# Ethernet_Phy.net
KiCad netlist of a schematic drawn in Altium Designer
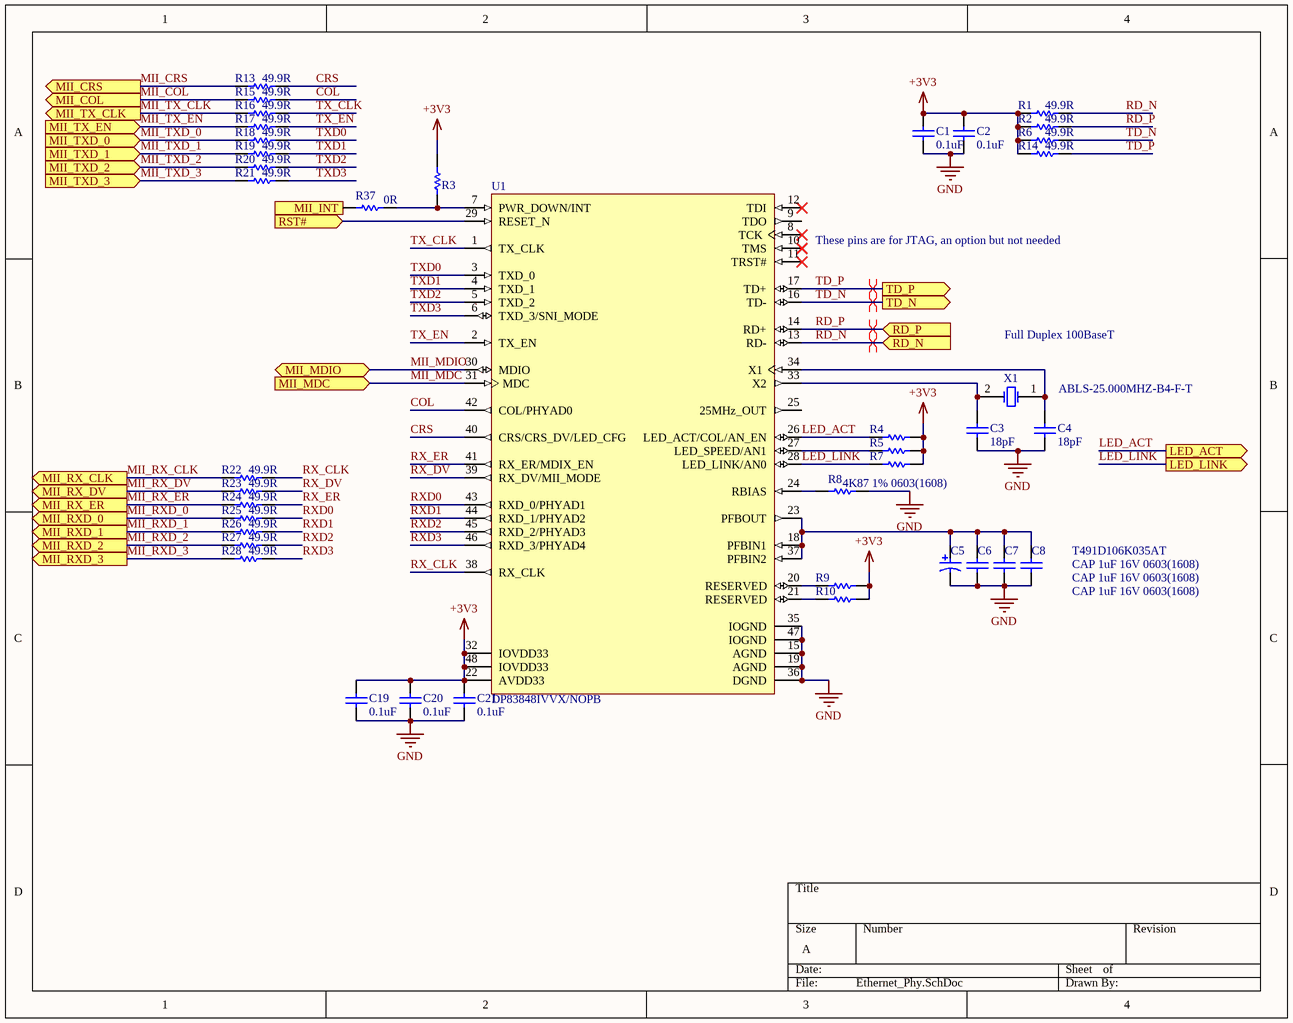
[diagram p0: Ethernet_Phy.SchDoc]

(export (version "E")
  (design (tool "Eeschema 10.0.6"))
  (components
    (comp (ref "C1")
      (value "0.1uF")
      (footprint "CAPC0603(1608)100_L")
      (description "0603 (1608 Metric) Chip Capacitor")
      (libsource (lib "Altium Content Vault") (part "CAP_5"))
    )
    (comp (ref "C2")
      (value "0.1uF")
      (footprint "CAPC0603(1608)100_L")
      (description "0603 (1608 Metric) Chip Capacitor")
      (libsource (lib "Altium Content Vault") (part "CAP_5"))
    )
    (comp (ref "C3")
      (value "18pF")
      (footprint "CAPC0603(1608)100_L")
      (description "0603 (1608 Metric) Chip Capacitor")
      (libsource (lib "Altium Content Vault") (part "CAP_5"))
    )
    (comp (ref "C4")
      (value "18pF")
      (footprint "CAPC0603(1608)100_L")
      (description "0603 (1608 Metric) Chip Capacitor")
      (libsource (lib "Altium Content Vault") (part "CAP_5"))
    )
    (comp (ref "C5")
      (value "T491D106K035AT")
      (footprint "KEMT-T491-D_L")
      (description "Tantalum Capacitor, 10 uF, +/- 10%, 35 V, -55 to 125 degC, 2-Pin SMD, RoHS, Tape and Reel")
      (fields (field (name "MANUFACTURER") "Kemet") (field (name "TOLERANCE") "20%"))
      (libsource (lib "Altium Content Vault") (part "CAP-P-2"))
    )
    (comp (ref "C6")
      (value "CAP 1uF 16V 0603(1608)")
      (footprint "CAPC0603(1608)100_N")
      (description "CAP 1uF 16V ±5% 0603 (1608 Metric) Thickness 1mm SMD")
      (fields (field (name "TOLERANCE") "Â±5%"))
      (libsource (lib "Altium Content Vault") (part "CAP"))
    )
    (comp (ref "C7")
      (value "CAP 1uF 16V 0603(1608)")
      (footprint "CAPC0603(1608)100_N")
      (description "CAP 1uF 16V ±5% 0603 (1608 Metric) Thickness 1mm SMD")
      (fields (field (name "TOLERANCE") "Â±5%"))
      (libsource (lib "Altium Content Vault") (part "CAP"))
    )
    (comp (ref "C8")
      (value "CAP 1uF 16V 0603(1608)")
      (footprint "CAPC0603(1608)100_N")
      (description "CAP 1uF 16V ±5% 0603 (1608 Metric) Thickness 1mm SMD")
      (fields (field (name "TOLERANCE") "Â±5%"))
      (libsource (lib "Altium Content Vault") (part "CAP"))
    )
    (comp (ref "C19")
      (value "0.1uF")
      (footprint "CAPC0603(1608)100_L")
      (description "0603 (1608 Metric) Chip Capacitor")
      (libsource (lib "Altium Content Vault") (part "CAP_5"))
    )
    (comp (ref "C20")
      (value "0.1uF")
      (footprint "CAPC0603(1608)100_L")
      (description "0603 (1608 Metric) Chip Capacitor")
      (libsource (lib "Altium Content Vault") (part "CAP_5"))
    )
    (comp (ref "C21")
      (value "0.1uF")
      (footprint "CAPC0603(1608)100_L")
      (description "0603 (1608 Metric) Chip Capacitor")
      (libsource (lib "Altium Content Vault") (part "CAP_5"))
    )
    (comp (ref "R1")
      (value "49.9R")
      (footprint "RESC0603(1608)_L")
      (description "0603 (1608 Metric) Chip Resistor")
      (libsource (lib "Altium Content Vault") (part "RES_3"))
    )
    (comp (ref "R2")
      (value "49.9R")
      (footprint "RESC0603(1608)_L")
      (description "0603 (1608 Metric) Chip Resistor")
      (libsource (lib "Altium Content Vault") (part "RES_3"))
    )
    (comp (ref "R3")
      (value "RC0603JR-072K2L")
      (footprint "RESC1608X55X25LL10T15")
      (description "Chip Resistor, 2.2 KOhm, +/- 5%, 0.1 W, -55 to 155 degC, 0603 (1608 Metric), RoHS, Tape and Reel")
      (fields (field (name "MANUFACTURER") "Yageo") (field (name "TOLERANCE") "5%"))
      (libsource (lib "Altium Content Vault") (part "RES-2"))
    )
    (comp (ref "R4")
      (value "RC0603JR-072K2L")
      (footprint "RESC1608X55X25LL10T15")
      (description "Chip Resistor, 2.2 KOhm, +/- 5%, 0.1 W, -55 to 155 degC, 0603 (1608 Metric), RoHS, Tape and Reel")
      (fields (field (name "MANUFACTURER") "Yageo") (field (name "TOLERANCE") "5%"))
      (libsource (lib "Altium Content Vault") (part "RES-2"))
    )
    (comp (ref "R5")
      (value "RC0603JR-072K2L")
      (footprint "RESC1608X55X25LL10T15")
      (description "Chip Resistor, 2.2 KOhm, +/- 5%, 0.1 W, -55 to 155 degC, 0603 (1608 Metric), RoHS, Tape and Reel")
      (fields (field (name "MANUFACTURER") "Yageo") (field (name "TOLERANCE") "5%"))
      (libsource (lib "Altium Content Vault") (part "RES-2"))
    )
    (comp (ref "R6")
      (value "49.9R")
      (footprint "RESC0603(1608)_L")
      (description "0603 (1608 Metric) Chip Resistor")
      (libsource (lib "Altium Content Vault") (part "RES_3"))
    )
    (comp (ref "R7")
      (value "RC0603JR-072K2L")
      (footprint "RESC1608X55X25LL10T15")
      (description "Chip Resistor, 2.2 KOhm, +/- 5%, 0.1 W, -55 to 155 degC, 0603 (1608 Metric), RoHS, Tape and Reel")
      (fields (field (name "MANUFACTURER") "Yageo") (field (name "TOLERANCE") "5%"))
      (libsource (lib "Altium Content Vault") (part "RES-2"))
    )
    (comp (ref "R8")
      (value "4K87 1% 0603(1608)")
      (footprint "RESC0603(1608)_N")
      (description "4K87 0.1W 1% 0603 (1608 Metric)  SMD")
      (fields (field (name "POWER") "0.1 W") (field (name "TOLERANCE") "1 %"))
      (libsource (lib "Altium Content Vault") (part "RES"))
    )
    (comp (ref "R9")
      (value "RC0603JR-072K2L")
      (footprint "RESC1608X55X25LL10T15")
      (description "Chip Resistor, 2.2 KOhm, +/- 5%, 0.1 W, -55 to 155 degC, 0603 (1608 Metric), RoHS, Tape and Reel")
      (fields (field (name "MANUFACTURER") "Yageo") (field (name "TOLERANCE") "5%"))
      (libsource (lib "Altium Content Vault") (part "RES-2"))
    )
    (comp (ref "R10")
      (value "RC0603JR-072K2L")
      (footprint "RESC1608X55X25LL10T15")
      (description "Chip Resistor, 2.2 KOhm, +/- 5%, 0.1 W, -55 to 155 degC, 0603 (1608 Metric), RoHS, Tape and Reel")
      (fields (field (name "MANUFACTURER") "Yageo") (field (name "TOLERANCE") "5%"))
      (libsource (lib "Altium Content Vault") (part "RES-2"))
    )
    (comp (ref "R13")
      (value "49.9R")
      (footprint "RESC0603(1608)_L")
      (description "0603 (1608 Metric) Chip Resistor")
      (libsource (lib "Altium Content Vault") (part "RES_3"))
    )
    (comp (ref "R14")
      (value "49.9R")
      (footprint "RESC0603(1608)_L")
      (description "0603 (1608 Metric) Chip Resistor")
      (libsource (lib "Altium Content Vault") (part "RES_3"))
    )
    (comp (ref "R15")
      (value "49.9R")
      (footprint "RESC0603(1608)_L")
      (description "0603 (1608 Metric) Chip Resistor")
      (libsource (lib "Altium Content Vault") (part "RES_3"))
    )
    (comp (ref "R16")
      (value "49.9R")
      (footprint "RESC0603(1608)_L")
      (description "0603 (1608 Metric) Chip Resistor")
      (libsource (lib "Altium Content Vault") (part "RES_3"))
    )
    (comp (ref "R17")
      (value "49.9R")
      (footprint "RESC0603(1608)_L")
      (description "0603 (1608 Metric) Chip Resistor")
      (libsource (lib "Altium Content Vault") (part "RES_3"))
    )
    (comp (ref "R18")
      (value "49.9R")
      (footprint "RESC0603(1608)_L")
      (description "0603 (1608 Metric) Chip Resistor")
      (libsource (lib "Altium Content Vault") (part "RES_3"))
    )
    (comp (ref "R19")
      (value "49.9R")
      (footprint "RESC0603(1608)_L")
      (description "0603 (1608 Metric) Chip Resistor")
      (libsource (lib "Altium Content Vault") (part "RES_3"))
    )
    (comp (ref "R20")
      (value "49.9R")
      (footprint "RESC0603(1608)_L")
      (description "0603 (1608 Metric) Chip Resistor")
      (libsource (lib "Altium Content Vault") (part "RES_3"))
    )
    (comp (ref "R21")
      (value "49.9R")
      (footprint "RESC0603(1608)_L")
      (description "0603 (1608 Metric) Chip Resistor")
      (libsource (lib "Altium Content Vault") (part "RES_3"))
    )
    (comp (ref "R22")
      (value "49.9R")
      (footprint "RESC0603(1608)_L")
      (description "0603 (1608 Metric) Chip Resistor")
      (libsource (lib "Altium Content Vault") (part "RES_3"))
    )
    (comp (ref "R23")
      (value "49.9R")
      (footprint "RESC0603(1608)_L")
      (description "0603 (1608 Metric) Chip Resistor")
      (libsource (lib "Altium Content Vault") (part "RES_3"))
    )
    (comp (ref "R24")
      (value "49.9R")
      (footprint "RESC0603(1608)_L")
      (description "0603 (1608 Metric) Chip Resistor")
      (libsource (lib "Altium Content Vault") (part "RES_3"))
    )
    (comp (ref "R25")
      (value "49.9R")
      (footprint "RESC0603(1608)_L")
      (description "0603 (1608 Metric) Chip Resistor")
      (libsource (lib "Altium Content Vault") (part "RES_3"))
    )
    (comp (ref "R26")
      (value "49.9R")
      (footprint "RESC0603(1608)_L")
      (description "0603 (1608 Metric) Chip Resistor")
      (libsource (lib "Altium Content Vault") (part "RES_3"))
    )
    (comp (ref "R27")
      (value "49.9R")
      (footprint "RESC0603(1608)_L")
      (description "0603 (1608 Metric) Chip Resistor")
      (libsource (lib "Altium Content Vault") (part "RES_3"))
    )
    (comp (ref "R28")
      (value "49.9R")
      (footprint "RESC0603(1608)_L")
      (description "0603 (1608 Metric) Chip Resistor")
      (libsource (lib "Altium Content Vault") (part "RES_3"))
    )
    (comp (ref "R37")
      (value "0R")
      (footprint "RESC0805(2012)_L")
      (description "0805 (2012 Metric) Chip Resistor")
      (fields (field (name "Comment") "RES0805"))
      (libsource (lib "Altium Content Vault") (part "RES_3"))
    )
    (comp (ref "U1")
      (value "DP83848IVVX/NOPB")
      (footprint "PT0048A_L")
      (fields (field (name "MANUFACTURER") "Texas Instruments"))
      (libsource (lib "Altium Content Vault") (part "IN-LNTX-DP83848IVV"))
    )
    (comp (ref "X1")
      (value "ABLS-25.000MHZ-B4-F-T")
      (footprint "ABRA-ABLS2-2_V")
      (fields (field (name "MANUFACTURER") "Abracon") (field (name "PARTNUMBER") "ABLS2-4.096MHZ-D4Y-T"))
      (libsource (lib "Altium Content Vault") (part "ABRA-XTAL_1-2-2"))
    )
  )
  (nets
    (net (code "1") (name "+3V3") (class "Default")
      (node (ref "C1") (pin "2") (pinfunction "2_2") (pintype "passive"))
      (node (ref "C19") (pin "2") (pinfunction "2_2") (pintype "passive"))
      (node (ref "C2") (pin "2") (pinfunction "2_2") (pintype "passive"))
      (node (ref "C20") (pin "2") (pinfunction "2_2") (pintype "passive"))
      (node (ref "C21") (pin "2") (pinfunction "2_2") (pintype "passive"))
      (node (ref "R1") (pin "1") (pinfunction "1_1") (pintype "passive"))
      (node (ref "R10") (pin "2") (pinfunction "2_2") (pintype "passive"))
      (node (ref "R14") (pin "1") (pinfunction "1_1") (pintype "passive"))
      (node (ref "R2") (pin "1") (pinfunction "1_1") (pintype "passive"))
      (node (ref "R3") (pin "2") (pinfunction "2_2") (pintype "passive"))
      (node (ref "R4") (pin "2") (pinfunction "2_2") (pintype "passive"))
      (node (ref "R5") (pin "2") (pinfunction "2_2") (pintype "passive"))
      (node (ref "R6") (pin "1") (pinfunction "1_1") (pintype "passive"))
      (node (ref "R7") (pin "2") (pinfunction "2_2") (pintype "passive"))
      (node (ref "R9") (pin "2") (pinfunction "2_2") (pintype "passive"))
      (node (ref "U1") (pin "22") (pinfunction "AVDD33_22") (pintype "power_in"))
      (node (ref "U1") (pin "32") (pinfunction "IOVDD33_32") (pintype "power_in"))
      (node (ref "U1") (pin "48") (pinfunction "IOVDD33_48") (pintype "power_in"))
    )
    (net (code "2") (name "/COL") (class "Default")
      (node (ref "R15") (pin "2") (pinfunction "2_2") (pintype "passive"))
      (node (ref "U1") (pin "42") (pinfunction "COL/PHYAD0_42") (pintype "output"))
    )
    (net (code "3") (name "/CRS") (class "Default")
      (node (ref "R13") (pin "2") (pinfunction "2_2") (pintype "passive"))
      (node (ref "U1") (pin "40") (pinfunction "CRS/CRS_DV/LED_CFG_40") (pintype "output"))
    )
    (net (code "4") (name "/LED_ACT") (class "Default")
      (node (ref "R4") (pin "1") (pinfunction "1_1") (pintype "passive"))
      (node (ref "U1") (pin "26") (pinfunction "LED_ACT/COL/AN_EN_26") (pintype "bidirectional"))
    )
    (net (code "5") (name "/LED_LINK") (class "Default")
      (node (ref "R7") (pin "1") (pinfunction "1_1") (pintype "passive"))
      (node (ref "U1") (pin "28") (pinfunction "LED_LINK/AN0_28") (pintype "bidirectional"))
    )
    (net (code "6") (name "/MII_COL") (class "Default")
      (node (ref "R15") (pin "1") (pinfunction "1_1") (pintype "passive"))
    )
    (net (code "7") (name "/MII_CRS") (class "Default")
      (node (ref "R13") (pin "1") (pinfunction "1_1") (pintype "passive"))
    )
    (net (code "8") (name "/MII_INT") (class "Default")
      (node (ref "R37") (pin "1") (pinfunction "1_1") (pintype "passive"))
    )
    (net (code "9") (name "/MII_MDC") (class "Default")
      (node (ref "U1") (pin "31") (pinfunction "MDC_31") (pintype "input"))
    )
    (net (code "10") (name "/MII_MDIO") (class "Default")
      (node (ref "U1") (pin "30") (pinfunction "MDIO_30") (pintype "bidirectional"))
    )
    (net (code "11") (name "/MII_RXD_0") (class "Default")
      (node (ref "R25") (pin "1") (pinfunction "1_1") (pintype "passive"))
    )
    (net (code "12") (name "/MII_RXD_1") (class "Default")
      (node (ref "R26") (pin "1") (pinfunction "1_1") (pintype "passive"))
    )
    (net (code "13") (name "/MII_RXD_2") (class "Default")
      (node (ref "R27") (pin "1") (pinfunction "1_1") (pintype "passive"))
    )
    (net (code "14") (name "/MII_RXD_3") (class "Default")
      (node (ref "R28") (pin "1") (pinfunction "1_1") (pintype "passive"))
    )
    (net (code "15") (name "/MII_RX_CLK") (class "Default")
      (node (ref "R22") (pin "1") (pinfunction "1_1") (pintype "passive"))
    )
    (net (code "16") (name "/MII_RX_DV") (class "Default")
      (node (ref "R23") (pin "1") (pinfunction "1_1") (pintype "passive"))
    )
    (net (code "17") (name "/MII_RX_ER") (class "Default")
      (node (ref "R24") (pin "1") (pinfunction "1_1") (pintype "passive"))
    )
    (net (code "18") (name "/MII_TXD_0") (class "Default")
      (node (ref "R18") (pin "1") (pinfunction "1_1") (pintype "passive"))
    )
    (net (code "19") (name "/MII_TXD_1") (class "Default")
      (node (ref "R19") (pin "1") (pinfunction "1_1") (pintype "passive"))
    )
    (net (code "20") (name "/MII_TXD_2") (class "Default")
      (node (ref "R20") (pin "1") (pinfunction "1_1") (pintype "passive"))
    )
    (net (code "21") (name "/MII_TXD_3") (class "Default")
      (node (ref "R21") (pin "1") (pinfunction "1_1") (pintype "passive"))
    )
    (net (code "22") (name "/MII_TX_CLK") (class "Default")
      (node (ref "R16") (pin "1") (pinfunction "1_1") (pintype "passive"))
    )
    (net (code "23") (name "/MII_TX_EN") (class "Default")
      (node (ref "R17") (pin "1") (pinfunction "1_1") (pintype "passive"))
    )
    (net (code "24") (name "/RD_N") (class "Default")
      (node (ref "R1") (pin "2") (pinfunction "2_2") (pintype "passive"))
      (node (ref "U1") (pin "13") (pinfunction "RD-_13") (pintype "bidirectional"))
    )
    (net (code "25") (name "/RD_P") (class "Default")
      (node (ref "R2") (pin "2") (pinfunction "2_2") (pintype "passive"))
      (node (ref "U1") (pin "14") (pinfunction "RD+_14") (pintype "bidirectional"))
    )
    (net (code "26") (name "/RST#") (class "Default")
      (node (ref "U1") (pin "29") (pinfunction "RESET_N_29") (pintype "input"))
    )
    (net (code "27") (name "/RXD0") (class "Default")
      (node (ref "R25") (pin "2") (pinfunction "2_2") (pintype "passive"))
      (node (ref "U1") (pin "43") (pinfunction "RXD_0/PHYAD1_43") (pintype "output"))
    )
    (net (code "28") (name "/RXD1") (class "Default")
      (node (ref "R26") (pin "2") (pinfunction "2_2") (pintype "passive"))
      (node (ref "U1") (pin "44") (pinfunction "RXD_1/PHYAD2_44") (pintype "output"))
    )
    (net (code "29") (name "/RXD2") (class "Default")
      (node (ref "R27") (pin "2") (pinfunction "2_2") (pintype "passive"))
      (node (ref "U1") (pin "45") (pinfunction "RXD_2/PHYAD3_45") (pintype "output"))
    )
    (net (code "30") (name "/RXD3") (class "Default")
      (node (ref "R28") (pin "2") (pinfunction "2_2") (pintype "passive"))
      (node (ref "U1") (pin "46") (pinfunction "RXD_3/PHYAD4_46") (pintype "output"))
    )
    (net (code "31") (name "/RX_CLK") (class "Default")
      (node (ref "R22") (pin "2") (pinfunction "2_2") (pintype "passive"))
      (node (ref "U1") (pin "38") (pinfunction "RX_CLK_38") (pintype "output"))
    )
    (net (code "32") (name "/RX_DV") (class "Default")
      (node (ref "R23") (pin "2") (pinfunction "2_2") (pintype "passive"))
      (node (ref "U1") (pin "39") (pinfunction "RX_DV/MII_MODE_39") (pintype "output"))
    )
    (net (code "33") (name "/RX_ER") (class "Default")
      (node (ref "R24") (pin "2") (pinfunction "2_2") (pintype "passive"))
      (node (ref "U1") (pin "41") (pinfunction "RX_ER/MDIX_EN_41") (pintype "output"))
    )
    (net (code "34") (name "/TD_N") (class "Default")
      (node (ref "R6") (pin "2") (pinfunction "2_2") (pintype "passive"))
      (node (ref "U1") (pin "16") (pinfunction "TD-_16") (pintype "bidirectional"))
    )
    (net (code "35") (name "/TD_P") (class "Default")
      (node (ref "R14") (pin "2") (pinfunction "2_2") (pintype "passive"))
      (node (ref "U1") (pin "17") (pinfunction "TD+_17") (pintype "bidirectional"))
    )
    (net (code "36") (name "/TXD0") (class "Default")
      (node (ref "R18") (pin "2") (pinfunction "2_2") (pintype "passive"))
      (node (ref "U1") (pin "3") (pinfunction "TXD_0_3") (pintype "input"))
    )
    (net (code "37") (name "/TXD1") (class "Default")
      (node (ref "R19") (pin "2") (pinfunction "2_2") (pintype "passive"))
      (node (ref "U1") (pin "4") (pinfunction "TXD_1_4") (pintype "input"))
    )
    (net (code "38") (name "/TXD2") (class "Default")
      (node (ref "R20") (pin "2") (pinfunction "2_2") (pintype "passive"))
      (node (ref "U1") (pin "5") (pinfunction "TXD_2_5") (pintype "input"))
    )
    (net (code "39") (name "/TXD3") (class "Default")
      (node (ref "R21") (pin "2") (pinfunction "2_2") (pintype "passive"))
      (node (ref "U1") (pin "6") (pinfunction "TXD_3/SNI_MODE_6") (pintype "bidirectional"))
    )
    (net (code "40") (name "/TX_CLK") (class "Default")
      (node (ref "R16") (pin "2") (pinfunction "2_2") (pintype "passive"))
      (node (ref "U1") (pin "1") (pinfunction "TX_CLK_1") (pintype "output"))
    )
    (net (code "41") (name "/TX_EN") (class "Default")
      (node (ref "R17") (pin "2") (pinfunction "2_2") (pintype "passive"))
      (node (ref "U1") (pin "2") (pinfunction "TX_EN_2") (pintype "input"))
    )
    (net (code "42") (name "GND") (class "Default")
      (node (ref "C1") (pin "1") (pinfunction "1_1") (pintype "passive"))
      (node (ref "C19") (pin "1") (pinfunction "1_1") (pintype "passive"))
      (node (ref "C2") (pin "1") (pinfunction "1_1") (pintype "passive"))
      (node (ref "C20") (pin "1") (pinfunction "1_1") (pintype "passive"))
      (node (ref "C21") (pin "1") (pinfunction "1_1") (pintype "passive"))
      (node (ref "C3") (pin "1") (pinfunction "1_1") (pintype "passive"))
      (node (ref "C4") (pin "1") (pinfunction "1_1") (pintype "passive"))
      (node (ref "C5") (pin "2") (pinfunction "2_2") (pintype "passive"))
      (node (ref "C6") (pin "1") (pinfunction "1_1") (pintype "passive"))
      (node (ref "C7") (pin "1") (pinfunction "1_1") (pintype "passive"))
      (node (ref "C8") (pin "1") (pinfunction "1_1") (pintype "passive"))
      (node (ref "R8") (pin "2") (pinfunction "2_2") (pintype "passive"))
      (node (ref "U1") (pin "15") (pinfunction "AGND_15") (pintype "power_in"))
      (node (ref "U1") (pin "19") (pinfunction "AGND_19") (pintype "power_in"))
      (node (ref "U1") (pin "35") (pinfunction "IOGND_35") (pintype "power_in"))
      (node (ref "U1") (pin "36") (pinfunction "DGND_36") (pintype "power_in"))
      (node (ref "U1") (pin "47") (pinfunction "IOGND_47") (pintype "power_in"))
    )
    (net (code "43") (name "Net-(R9-Pad1)") (class "Default")
      (node (ref "R9") (pin "1") (pinfunction "1_1") (pintype "passive"))
      (node (ref "U1") (pin "20") (pinfunction "RESERVED_20") (pintype "bidirectional"))
    )
    (net (code "44") (name "Net-(R10-Pad1)") (class "Default")
      (node (ref "R10") (pin "1") (pinfunction "1_1") (pintype "passive"))
      (node (ref "U1") (pin "21") (pinfunction "RESERVED_21") (pintype "bidirectional"))
    )
    (net (code "45") (name "Net-(U1-LED_SPEED{slash}AN1)") (class "Default")
      (node (ref "R5") (pin "1") (pinfunction "1_1") (pintype "passive"))
      (node (ref "U1") (pin "27") (pinfunction "LED_SPEED/AN1_27") (pintype "bidirectional"))
    )
    (net (code "46") (name "Net-(U1-PFBIN1)") (class "Default")
      (node (ref "C5") (pin "1") (pinfunction "1_1") (pintype "passive"))
      (node (ref "C6") (pin "2") (pinfunction "2_2") (pintype "passive"))
      (node (ref "C7") (pin "2") (pinfunction "2_2") (pintype "passive"))
      (node (ref "C8") (pin "2") (pinfunction "2_2") (pintype "passive"))
      (node (ref "U1") (pin "18") (pinfunction "PFBIN1_18") (pintype "input"))
      (node (ref "U1") (pin "23") (pinfunction "PFBOUT_23") (pintype "output"))
      (node (ref "U1") (pin "37") (pinfunction "PFBIN2_37") (pintype "input"))
    )
    (net (code "47") (name "Net-(U1-PWR_DOWN{slash}INT)") (class "Default")
      (node (ref "R3") (pin "1") (pinfunction "1_1") (pintype "passive"))
      (node (ref "R37") (pin "2") (pinfunction "2_2") (pintype "passive"))
      (node (ref "U1") (pin "7") (pinfunction "PWR_DOWN/INT_7") (pintype "input"))
    )
    (net (code "48") (name "Net-(U1-RBIAS)") (class "Default")
      (node (ref "R8") (pin "1") (pinfunction "1_1") (pintype "passive"))
      (node (ref "U1") (pin "24") (pinfunction "RBIAS_24") (pintype "input"))
    )
    (net (code "49") (name "Net-(U1-X1)") (class "Default")
      (node (ref "C4") (pin "2") (pinfunction "2_2") (pintype "passive"))
      (node (ref "U1") (pin "34") (pinfunction "X1_34") (pintype "input"))
      (node (ref "X1") (pin "1") (pinfunction "X1_1") (pintype "passive"))
    )
    (net (code "50") (name "Net-(U1-X2)") (class "Default")
      (node (ref "C3") (pin "2") (pinfunction "2_2") (pintype "passive"))
      (node (ref "U1") (pin "33") (pinfunction "X2_33") (pintype "output"))
      (node (ref "X1") (pin "2") (pinfunction "X2_2") (pintype "passive"))
    )
    (net (code "51") (name "unconnected-(U1-25MHz_OUT-Pad25)") (class "Default")
      (node (ref "U1") (pin "25") (pinfunction "25MHz_OUT_25") (pintype "output"))
    )
    (net (code "52") (name "unconnected-(U1-TCK-Pad8)") (class "Default")
      (node (ref "U1") (pin "8") (pinfunction "TCK_8") (pintype "input+no_connect"))
    )
    (net (code "53") (name "unconnected-(U1-TDI-Pad12)") (class "Default")
      (node (ref "U1") (pin "12") (pinfunction "TDI_12") (pintype "input+no_connect"))
    )
    (net (code "54") (name "unconnected-(U1-TDO-Pad9)") (class "Default")
      (node (ref "U1") (pin "9") (pinfunction "TDO_9") (pintype "output"))
    )
    (net (code "55") (name "unconnected-(U1-TMS-Pad10)") (class "Default")
      (node (ref "U1") (pin "10") (pinfunction "TMS_10") (pintype "input+no_connect"))
    )
    (net (code "56") (name "unconnected-(U1-TRST#-Pad11)") (class "Default")
      (node (ref "U1") (pin "11") (pinfunction "TRST#_11") (pintype "input+no_connect"))
    )
  )
)
